# IP5209_Charge1s_Out2s.net
KiCad netlist of a schematic drawn in Altium Designer
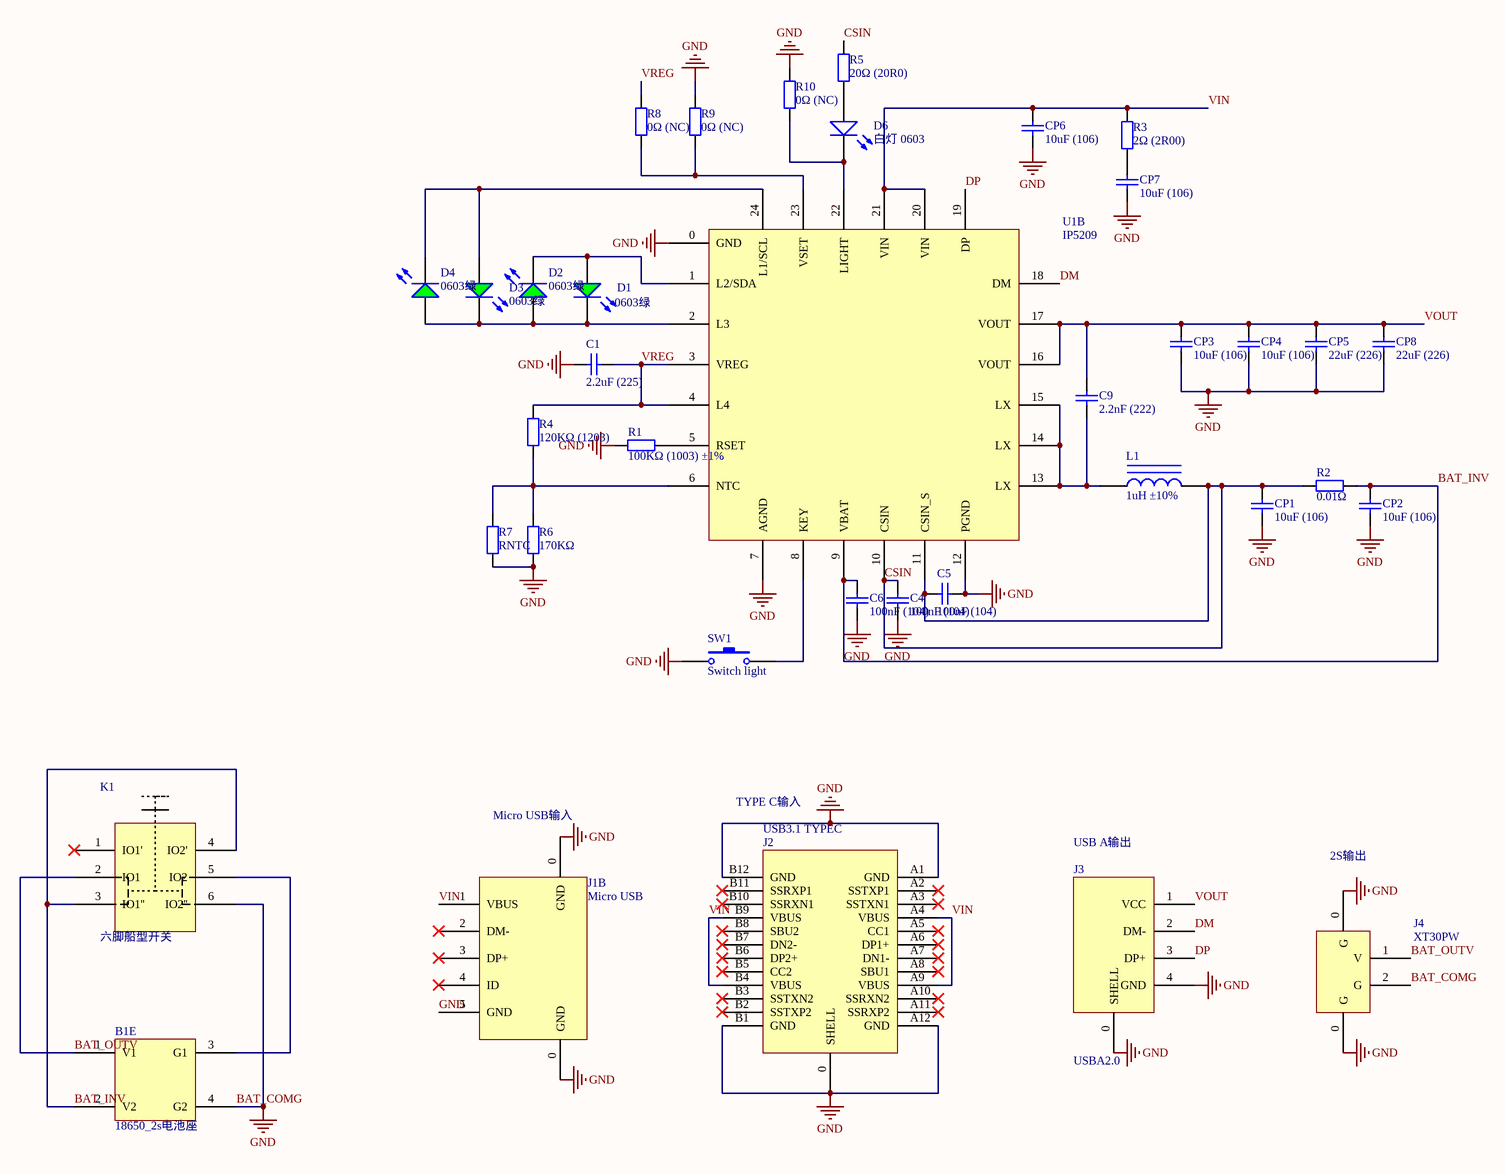
[diagram p0: IP5209_Charge1s_Out2s.SchDoc]

(export (version "E")
  (design (tool "Eeschema 10.0.6"))
  (components
    (comp (ref "B1")
      (value "18650_2s电池座")
      (footprint "186502s电池座")
      (libsource (lib "MiniQuadrotorSchlib") (part "18650_2s电池座"))
    )
    (comp (ref "C1")
      (value "2.2uF (225)")
      (footprint "0603_C")
      (description "贴片电容")
      (libsource (lib "Miscellaneous Devices LC") (part "0603 2.2uF (225) 10% 16V"))
    )
    (comp (ref "C4")
      (value "100nF (104)")
      (footprint "0603_C")
      (description "贴片电容")
      (libsource (lib "Miscellaneous Devices LC") (part "0603 100nF (104) 10% 50V"))
    )
    (comp (ref "C5")
      (value "100nF (104)")
      (footprint "0603_C")
      (description "贴片电容")
      (libsource (lib "Miscellaneous Devices LC") (part "0603 100nF (104) 10% 50V"))
    )
    (comp (ref "C6")
      (value "100nF (104)")
      (footprint "0603_C")
      (description "贴片电容")
      (libsource (lib "Miscellaneous Devices LC") (part "0603 100nF (104) 10% 50V"))
    )
    (comp (ref "C9")
      (value "2.2nF (222)")
      (footprint "0603_C")
      (description "贴片电容")
      (libsource (lib "Miscellaneous Devices LC") (part "0603 2.2nF (222) 10% 50V"))
    )
    (comp (ref "CP1")
      (value "10uF (106)")
      (footprint "0603_C")
      (description "贴片电容")
      (libsource (lib "Miscellaneous Devices LC") (part "0603 10uF (106) 10% 10V"))
    )
    (comp (ref "CP2")
      (value "10uF (106)")
      (footprint "0603_C")
      (description "贴片电容")
      (libsource (lib "Miscellaneous Devices LC") (part "0603 10uF (106) 10% 10V"))
    )
    (comp (ref "CP3")
      (value "10uF (106)")
      (footprint "0603_C")
      (description "贴片电容")
      (libsource (lib "Miscellaneous Devices LC") (part "0603 10uF (106) 10% 10V"))
    )
    (comp (ref "CP4")
      (value "10uF (106)")
      (footprint "0603_C")
      (description "贴片电容")
      (libsource (lib "Miscellaneous Devices LC") (part "0603 10uF (106) 10% 10V"))
    )
    (comp (ref "CP5")
      (value "22uF (226)")
      (footprint "0603_C")
      (description "贴片电容")
      (libsource (lib "Miscellaneous Devices LC") (part "0603 22uF (226) 20% 6.3V"))
    )
    (comp (ref "CP6")
      (value "10uF (106)")
      (footprint "0603_C")
      (description "贴片电容")
      (libsource (lib "Miscellaneous Devices LC") (part "0603 10uF (106) 10% 10V"))
    )
    (comp (ref "CP7")
      (value "10uF (106)")
      (footprint "0603_C")
      (description "贴片电容")
      (libsource (lib "Miscellaneous Devices LC") (part "0603 10uF (106) 10% 10V"))
    )
    (comp (ref "CP8")
      (value "22uF (226)")
      (footprint "0603_C")
      (description "贴片电容")
      (libsource (lib "Miscellaneous Devices LC") (part "0603 22uF (226) 20% 6.3V"))
    )
    (comp (ref "D1")
      (value "0603绿")
      (footprint "0603_LED_S1")
      (description "发光二极管")
      (libsource (lib "Miscellaneous Devices LC") (part "0603 绿灯"))
    )
    (comp (ref "D2")
      (value "0603绿")
      (footprint "0603_LED_S1")
      (description "发光二极管")
      (libsource (lib "Miscellaneous Devices LC") (part "0603 绿灯"))
    )
    (comp (ref "D3")
      (value "0603绿")
      (footprint "0603_LED_S1")
      (description "发光二极管")
      (libsource (lib "Miscellaneous Devices LC") (part "0603 绿灯"))
    )
    (comp (ref "D4")
      (value "0603绿")
      (footprint "0603_LED_S1")
      (description "发光二极管")
      (libsource (lib "Miscellaneous Devices LC") (part "0603 绿灯"))
    )
    (comp (ref "D6")
      (value "白灯 0603")
      (footprint "0603_LED_S1")
      (description "发光二极管")
      (libsource (lib "Miscellaneous Devices LC") (part "0603 白灯"))
    )
    (comp (ref "J1")
      (value "Micro USB")
      (footprint "MicroUSB-贴片")
      (libsource (lib "MiniQuadrotorSchlib") (part "Micro USB"))
    )
    (comp (ref "J2")
      (value "USB3.1 TYPEC")
      (footprint "USB3.1 TYPE-C 26P 母座")
      (description "USB 3.1 TYPE-C 26P 母座 90度 带卡扣 焊板式 4固定脚 无边双向")
      (libsource (lib "MiniQuadrotorSchlib") (part "USB3.1 TYPEC"))
    )
    (comp (ref "J3")
      (value "USBA2.0")
      (footprint "USB2.0 A母全贴无边")
      (description "USB2.0 A母全贴无边-AF 13.9 MM 2固定贴片 卷边")
      (libsource (lib "MiniQuadrotorSchlib") (part "USBA2.0"))
    )
    (comp (ref "J4")
      (value "XT30PW")
      (footprint "XT30PW-F")
      (libsource (lib "MiniQuadrotorSchlib") (part "XT30PW"))
    )
    (comp (ref "K1")
      (value "六脚船型开关")
      (footprint "六脚船型开关21*15")
      (libsource (lib "MiniQuadrotorSchlib") (part "六脚船型开关"))
    )
    (comp (ref "L1")
      (value "1uH ±10%")
      (footprint "22UH L")
      (description "贴片电感")
      (libsource (lib "Miscellaneous Devices LC") (part "0805 1uH 10%"))
    )
    (comp (ref "R1")
      (value "100KΩ (1003) ±1%")
      (footprint "0603_R")
      (description "贴片电阻")
      (libsource (lib "Miscellaneous Devices LC") (part "0603 100KΩ (1003) 1%"))
    )
    (comp (ref "R2")
      (value "0.01Ω")
      (footprint "1206_R")
      (description "贴片电阻")
      (libsource (lib "Miscellaneous Devices LC") (part "1206 0.1Ω (R100) 1%"))
    )
    (comp (ref "R3")
      (value "2Ω (2R00)")
      (footprint "0603_R")
      (description "贴片电阻")
      (libsource (lib "Miscellaneous Devices LC") (part "0603 2Ω (2R00) 1%"))
    )
    (comp (ref "R4")
      (value "120KΩ (1203)")
      (footprint "0603_R")
      (description "贴片电阻")
      (libsource (lib "Miscellaneous Devices LC") (part "0603 120KΩ (1203) 1%"))
    )
    (comp (ref "R5")
      (value "20Ω (20R0)")
      (footprint "0603_R")
      (description "贴片电阻")
      (libsource (lib "Miscellaneous Devices LC") (part "0603 20Ω (20R0) 1%"))
    )
    (comp (ref "R6")
      (value "170KΩ")
      (footprint "0603_R")
      (description "贴片电阻")
      (libsource (lib "Miscellaneous Devices LC") (part "0603 120KΩ (1203) 1%"))
    )
    (comp (ref "R7")
      (value "RNTC")
      (footprint "0603_R")
      (description "贴片电阻")
      (libsource (lib "Miscellaneous Devices LC") (part "0603 0Ω (0R0) 1%"))
    )
    (comp (ref "R8")
      (value "0Ω (NC)")
      (footprint "0603_R")
      (description "贴片电阻")
      (libsource (lib "Miscellaneous Devices LC") (part "0603 0Ω (0R0) 1%"))
    )
    (comp (ref "R9")
      (value "0Ω (NC)")
      (footprint "0603_R")
      (description "贴片电阻")
      (libsource (lib "Miscellaneous Devices LC") (part "0603 0Ω (0R0) 1%"))
    )
    (comp (ref "R10")
      (value "0Ω (NC)")
      (footprint "0603_R")
      (description "贴片电阻")
      (libsource (lib "Miscellaneous Devices LC") (part "0603 0Ω (0R0) 1%"))
    )
    (comp (ref "SW1")
      (value "Switch light")
      (footprint "Integrated_Library:KEY")
      (description "Switch")
      (fields (field (name "PUBLISHER") "Altium Limited"))
      (libsource (lib "Miscellaneous Devices") (part "SW-PB"))
    )
    (comp (ref "U1")
      (value "IP5209")
      (footprint "IP5209")
      (libsource (lib "MiniQuadrotorSchlib") (part "IP5209"))
    )
  )
  (nets
    (net (code "1") (name "/BAT_INV") (class "Default")
      (node (ref "B1") (pin "2") (pinfunction "V2_2") (pintype "passive"))
      (node (ref "C6") (pin "2") (pinfunction "2_2") (pintype "passive"))
      (node (ref "CP2") (pin "2") (pinfunction "2_2") (pintype "passive"))
      (node (ref "K1") (pin "3") (pinfunction "IO1''_3") (pintype "passive"))
      (node (ref "K1") (pin "4") (pinfunction "IO2'_4") (pintype "passive"))
      (node (ref "R2") (pin "2") (pinfunction "2_2") (pintype "passive"))
      (node (ref "U1") (pin "9") (pinfunction "VBAT_9") (pintype "passive"))
    )
    (net (code "2") (name "/BAT_OUTV") (class "Default")
      (node (ref "B1") (pin "1") (pinfunction "V1_1") (pintype "passive"))
      (node (ref "J4") (pin "1") (pinfunction "V_1") (pintype "passive"))
      (node (ref "K1") (pin "2") (pinfunction "IO1_2") (pintype "passive"))
    )
    (net (code "3") (name "/CSIN") (class "Default")
      (node (ref "C4") (pin "2") (pinfunction "2_2") (pintype "passive"))
      (node (ref "C5") (pin "1") (pinfunction "1_1") (pintype "passive"))
      (node (ref "CP1") (pin "2") (pinfunction "2_2") (pintype "passive"))
      (node (ref "L1") (pin "2") (pinfunction "2_2") (pintype "passive"))
      (node (ref "R2") (pin "1") (pinfunction "1_1") (pintype "passive"))
      (node (ref "R5") (pin "2") (pinfunction "2_2") (pintype "passive"))
      (node (ref "U1") (pin "10") (pinfunction "CSIN_10") (pintype "passive"))
      (node (ref "U1") (pin "11") (pinfunction "CSIN_S_11") (pintype "passive"))
    )
    (net (code "4") (name "/DM") (class "Default")
      (node (ref "J3") (pin "2") (pinfunction "DM-_2") (pintype "passive"))
      (node (ref "U1") (pin "18") (pinfunction "DM_18") (pintype "passive"))
    )
    (net (code "5") (name "/DP") (class "Default")
      (node (ref "J3") (pin "3") (pinfunction "DP+_3") (pintype "passive"))
      (node (ref "U1") (pin "19") (pinfunction "DP_19") (pintype "passive"))
    )
    (net (code "6") (name "/VIN") (class "Default")
      (node (ref "CP6") (pin "2") (pinfunction "2_2") (pintype "passive"))
      (node (ref "J1") (pin "1") (pinfunction "VBUS_1") (pintype "passive"))
      (node (ref "J2") (pin "A4") (pinfunction "VBUS_A4") (pintype "passive"))
      (node (ref "J2") (pin "A9") (pinfunction "VBUS_A9") (pintype "passive"))
      (node (ref "J2") (pin "B4") (pinfunction "VBUS_B4") (pintype "passive"))
      (node (ref "J2") (pin "B9") (pinfunction "VBUS_B9") (pintype "passive"))
      (node (ref "R3") (pin "2") (pinfunction "2_2") (pintype "passive"))
      (node (ref "U1") (pin "20") (pinfunction "VIN_20") (pintype "passive"))
      (node (ref "U1") (pin "21") (pinfunction "VIN_21") (pintype "passive"))
    )
    (net (code "7") (name "/VOUT") (class "Default")
      (node (ref "C9") (pin "2") (pinfunction "2_2") (pintype "passive"))
      (node (ref "CP3") (pin "2") (pinfunction "2_2") (pintype "passive"))
      (node (ref "CP4") (pin "2") (pinfunction "2_2") (pintype "passive"))
      (node (ref "CP5") (pin "1") (pinfunction "1_1") (pintype "passive"))
      (node (ref "CP8") (pin "1") (pinfunction "1_1") (pintype "passive"))
      (node (ref "J3") (pin "1") (pinfunction "VCC_1") (pintype "passive"))
      (node (ref "U1") (pin "16") (pinfunction "VOUT_16") (pintype "passive"))
      (node (ref "U1") (pin "17") (pinfunction "VOUT_17") (pintype "passive"))
    )
    (net (code "8") (name "/VREG") (class "Default")
      (node (ref "C1") (pin "2") (pinfunction "2_2") (pintype "passive"))
      (node (ref "R4") (pin "2") (pinfunction "2_2") (pintype "passive"))
      (node (ref "R8") (pin "2") (pinfunction "2_2") (pintype "passive"))
      (node (ref "U1") (pin "3") (pinfunction "VREG_3") (pintype "passive"))
      (node (ref "U1") (pin "4") (pinfunction "L4_4") (pintype "passive"))
    )
    (net (code "9") (name "GND") (class "Default")
      (node (ref "B1") (pin "4") (pinfunction "G2_4") (pintype "passive"))
      (node (ref "C1") (pin "1") (pinfunction "1_1") (pintype "passive"))
      (node (ref "C4") (pin "1") (pinfunction "1_1") (pintype "passive"))
      (node (ref "C5") (pin "2") (pinfunction "2_2") (pintype "passive"))
      (node (ref "C6") (pin "1") (pinfunction "1_1") (pintype "passive"))
      (node (ref "CP1") (pin "1") (pinfunction "1_1") (pintype "passive"))
      (node (ref "CP2") (pin "1") (pinfunction "1_1") (pintype "passive"))
      (node (ref "CP3") (pin "1") (pinfunction "1_1") (pintype "passive"))
      (node (ref "CP4") (pin "1") (pinfunction "1_1") (pintype "passive"))
      (node (ref "CP5") (pin "2") (pinfunction "2_2") (pintype "passive"))
      (node (ref "CP6") (pin "1") (pinfunction "1_1") (pintype "passive"))
      (node (ref "CP7") (pin "1") (pinfunction "1_1") (pintype "passive"))
      (node (ref "CP8") (pin "2") (pinfunction "2_2") (pintype "passive"))
      (node (ref "J1") (pin "0") (pinfunction "GND_0") (pintype "passive"))
      (node (ref "J1") (pin "5") (pinfunction "GND_5") (pintype "passive"))
      (node (ref "J2") (pin "0") (pinfunction "SHELL_0") (pintype "passive"))
      (node (ref "J2") (pin "A1") (pinfunction "GND_A1") (pintype "passive"))
      (node (ref "J2") (pin "A12") (pinfunction "GND_A12") (pintype "passive"))
      (node (ref "J2") (pin "B1") (pinfunction "GND_B1") (pintype "passive"))
      (node (ref "J2") (pin "B12") (pinfunction "GND_B12") (pintype "passive"))
      (node (ref "J3") (pin "0") (pinfunction "SHELL_0") (pintype "passive"))
      (node (ref "J3") (pin "4") (pinfunction "GND_4") (pintype "passive"))
      (node (ref "J4") (pin "0") (pinfunction "G_0") (pintype "passive"))
      (node (ref "J4") (pin "2") (pinfunction "G_2") (pintype "passive"))
      (node (ref "K1") (pin "6") (pinfunction "IO2''_6") (pintype "passive"))
      (node (ref "R1") (pin "1") (pinfunction "1_1") (pintype "passive"))
      (node (ref "R10") (pin "2") (pinfunction "2_2") (pintype "passive"))
      (node (ref "R6") (pin "1") (pinfunction "1_1") (pintype "passive"))
      (node (ref "R7") (pin "1") (pinfunction "1_1") (pintype "passive"))
      (node (ref "R9") (pin "2") (pinfunction "2_2") (pintype "passive"))
      (node (ref "SW1") (pin "1") (pinfunction "1_1") (pintype "passive"))
      (node (ref "U1") (pin "0") (pinfunction "GND_0") (pintype "passive"))
      (node (ref "U1") (pin "12") (pinfunction "PGND_12") (pintype "passive"))
      (node (ref "U1") (pin "7") (pinfunction "AGND_7") (pintype "passive"))
    )
    (net (code "10") (name "Net-(B1E-G1)") (class "Default")
      (node (ref "B1") (pin "3") (pinfunction "G1_3") (pintype "passive"))
      (node (ref "K1") (pin "5") (pinfunction "IO2_5") (pintype "passive"))
    )
    (net (code "11") (name "Net-(C9-Pad1)") (class "Default")
      (node (ref "C9") (pin "1") (pinfunction "1_1") (pintype "passive"))
      (node (ref "L1") (pin "1") (pinfunction "1_1") (pintype "passive"))
      (node (ref "U1") (pin "13") (pinfunction "LX_13") (pintype "passive"))
      (node (ref "U1") (pin "14") (pinfunction "LX_14") (pintype "passive"))
      (node (ref "U1") (pin "15") (pinfunction "LX_15") (pintype "passive"))
    )
    (net (code "12") (name "Net-(CP7-Pad2)") (class "Default")
      (node (ref "CP7") (pin "2") (pinfunction "2_2") (pintype "passive"))
      (node (ref "R3") (pin "1") (pinfunction "1_1") (pintype "passive"))
    )
    (net (code "13") (name "Net-(D6-PadA)") (class "Default")
      (node (ref "D6") (pin "A") (pinfunction "A_A") (pintype "passive"))
      (node (ref "R5") (pin "1") (pinfunction "1_1") (pintype "passive"))
    )
    (net (code "14") (name "Net-(U1B-KEY)") (class "Default")
      (node (ref "SW1") (pin "2") (pinfunction "2_2") (pintype "passive"))
      (node (ref "U1") (pin "8") (pinfunction "KEY_8") (pintype "passive"))
    )
    (net (code "15") (name "Net-(U1B-L1{slash}SCL)") (class "Default")
      (node (ref "D3") (pin "A") (pinfunction "A_A") (pintype "passive"))
      (node (ref "D4") (pin "K") (pinfunction "K_K") (pintype "passive"))
      (node (ref "U1") (pin "24") (pinfunction "L1/SCL_24") (pintype "passive"))
    )
    (net (code "16") (name "Net-(U1B-L2{slash}SDA)") (class "Default")
      (node (ref "D1") (pin "A") (pinfunction "A_A") (pintype "passive"))
      (node (ref "D2") (pin "K") (pinfunction "K_K") (pintype "passive"))
      (node (ref "U1") (pin "1") (pinfunction "L2/SDA_1") (pintype "passive"))
    )
    (net (code "17") (name "Net-(U1B-L3)") (class "Default")
      (node (ref "D1") (pin "K") (pinfunction "K_K") (pintype "passive"))
      (node (ref "D2") (pin "A") (pinfunction "A_A") (pintype "passive"))
      (node (ref "D3") (pin "K") (pinfunction "K_K") (pintype "passive"))
      (node (ref "D4") (pin "A") (pinfunction "A_A") (pintype "passive"))
      (node (ref "U1") (pin "2") (pinfunction "L3_2") (pintype "passive"))
    )
    (net (code "18") (name "Net-(U1B-LIGHT)") (class "Default")
      (node (ref "D6") (pin "K") (pinfunction "K_K") (pintype "passive"))
      (node (ref "R10") (pin "1") (pinfunction "1_1") (pintype "passive"))
      (node (ref "U1") (pin "22") (pinfunction "LIGHT_22") (pintype "passive"))
    )
    (net (code "19") (name "Net-(U1B-NTC)") (class "Default")
      (node (ref "R4") (pin "1") (pinfunction "1_1") (pintype "passive"))
      (node (ref "R6") (pin "2") (pinfunction "2_2") (pintype "passive"))
      (node (ref "R7") (pin "2") (pinfunction "2_2") (pintype "passive"))
      (node (ref "U1") (pin "6") (pinfunction "NTC_6") (pintype "passive"))
    )
    (net (code "20") (name "Net-(U1B-RSET)") (class "Default")
      (node (ref "R1") (pin "2") (pinfunction "2_2") (pintype "passive"))
      (node (ref "U1") (pin "5") (pinfunction "RSET_5") (pintype "passive"))
    )
    (net (code "21") (name "Net-(U1B-VSET)") (class "Default")
      (node (ref "R8") (pin "1") (pinfunction "1_1") (pintype "passive"))
      (node (ref "R9") (pin "1") (pinfunction "1_1") (pintype "passive"))
      (node (ref "U1") (pin "23") (pinfunction "VSET_23") (pintype "passive"))
    )
    (net (code "22") (name "unconnected-(J1B-DM--Pad2)") (class "Default")
      (node (ref "J1") (pin "2") (pinfunction "DM-_2") (pintype "passive+no_connect"))
    )
    (net (code "23") (name "unconnected-(J1B-DP+-Pad3)") (class "Default")
      (node (ref "J1") (pin "3") (pinfunction "DP+_3") (pintype "passive+no_connect"))
    )
    (net (code "24") (name "unconnected-(J1B-ID-Pad4)") (class "Default")
      (node (ref "J1") (pin "4") (pinfunction "ID_4") (pintype "passive+no_connect"))
    )
    (net (code "25") (name "unconnected-(J2-CC1-PadA5)") (class "Default")
      (node (ref "J2") (pin "A5") (pinfunction "CC1_A5") (pintype "passive+no_connect"))
    )
    (net (code "26") (name "unconnected-(J2-CC2-PadB5)") (class "Default")
      (node (ref "J2") (pin "B5") (pinfunction "CC2_B5") (pintype "passive+no_connect"))
    )
    (net (code "27") (name "unconnected-(J2-DN1--PadA7)") (class "Default")
      (node (ref "J2") (pin "A7") (pinfunction "DN1-_A7") (pintype "passive+no_connect"))
    )
    (net (code "28") (name "unconnected-(J2-DN2--PadB7)") (class "Default")
      (node (ref "J2") (pin "B7") (pinfunction "DN2-_B7") (pintype "passive+no_connect"))
    )
    (net (code "29") (name "unconnected-(J2-DP1+-PadA6)") (class "Default")
      (node (ref "J2") (pin "A6") (pinfunction "DP1+_A6") (pintype "passive+no_connect"))
    )
    (net (code "30") (name "unconnected-(J2-DP2+-PadB6)") (class "Default")
      (node (ref "J2") (pin "B6") (pinfunction "DP2+_B6") (pintype "passive+no_connect"))
    )
    (net (code "31") (name "unconnected-(J2-SBU1-PadA8)") (class "Default")
      (node (ref "J2") (pin "A8") (pinfunction "SBU1_A8") (pintype "passive+no_connect"))
    )
    (net (code "32") (name "unconnected-(J2-SBU2-PadB8)") (class "Default")
      (node (ref "J2") (pin "B8") (pinfunction "SBU2_B8") (pintype "passive+no_connect"))
    )
    (net (code "33") (name "unconnected-(J2-SSRXN1-PadB10)") (class "Default")
      (node (ref "J2") (pin "B10") (pinfunction "SSRXN1_B10") (pintype "passive+no_connect"))
    )
    (net (code "34") (name "unconnected-(J2-SSRXN2-PadA10)") (class "Default")
      (node (ref "J2") (pin "A10") (pinfunction "SSRXN2_A10") (pintype "passive+no_connect"))
    )
    (net (code "35") (name "unconnected-(J2-SSRXP1-PadB11)") (class "Default")
      (node (ref "J2") (pin "B11") (pinfunction "SSRXP1_B11") (pintype "passive+no_connect"))
    )
    (net (code "36") (name "unconnected-(J2-SSRXP2-PadA11)") (class "Default")
      (node (ref "J2") (pin "A11") (pinfunction "SSRXP2_A11") (pintype "passive+no_connect"))
    )
    (net (code "37") (name "unconnected-(J2-SSTXN1-PadA3)") (class "Default")
      (node (ref "J2") (pin "A3") (pinfunction "SSTXN1_A3") (pintype "passive+no_connect"))
    )
    (net (code "38") (name "unconnected-(J2-SSTXN2-PadB3)") (class "Default")
      (node (ref "J2") (pin "B3") (pinfunction "SSTXN2_B3") (pintype "passive+no_connect"))
    )
    (net (code "39") (name "unconnected-(J2-SSTXP1-PadA2)") (class "Default")
      (node (ref "J2") (pin "A2") (pinfunction "SSTXP1_A2") (pintype "passive+no_connect"))
    )
    (net (code "40") (name "unconnected-(J2-SSTXP2-PadB2)") (class "Default")
      (node (ref "J2") (pin "B2") (pinfunction "SSTXP2_B2") (pintype "passive+no_connect"))
    )
    (net (code "41") (name "unconnected-(K1-IO1'-Pad1)") (class "Default")
      (node (ref "K1") (pin "1") (pinfunction "IO1'_1") (pintype "passive+no_connect"))
    )
  )
)
